# power_mux-v2.net
KiCad netlist of a schematic drawn in EAGLE
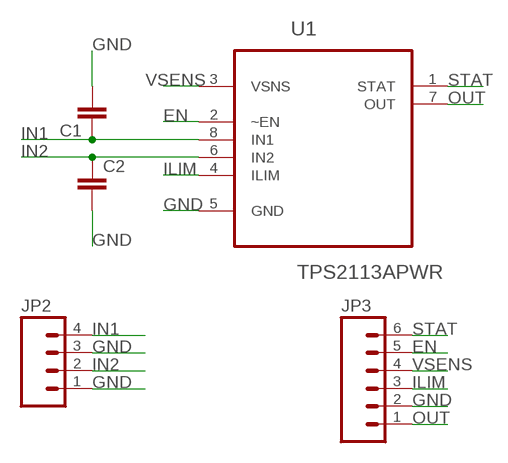
[diagram p0: schematic, sheet 1]

(export (version "E")
  (design (tool "Eeschema 10.0.6"))
  (components
    (comp (ref "C1")
      (value "CAP0805")
      (footprint "eagle-import:0805")
      (libsource (lib "eagle-import") (part "CAP0805"))
    )
    (comp (ref "C2")
      (value "CAP0805")
      (footprint "eagle-import:0805")
      (libsource (lib "eagle-import") (part "CAP0805"))
    )
    (comp (ref "JP2")
      (value "M04PTH")
      (footprint "eagle-import:1X04")
      (libsource (lib "eagle-import") (part "M04PTH"))
    )
    (comp (ref "JP3")
      (value "M06SIP")
      (footprint "eagle-import:1X06")
      (libsource (lib "eagle-import") (part "M06SIP"))
    )
    (comp (ref "U1")
      (value "TPS2113APWR")
      (footprint "eagle-import:SOP65P640X120-8N")
      (libsource (lib "eagle-import") (part "TPS2113APWR"))
    )
  )
  (nets
    (net (code "1") (name "/EN") (class "Default")
      (node (ref "JP3") (pin "5") (pinfunction "5_5") (pintype "passive"))
      (node (ref "U1") (pin "2") (pinfunction "~{EN}_2") (pintype "input"))
    )
    (net (code "2") (name "/GND") (class "Default")
      (node (ref "C1") (pin "2") (pinfunction "2_2") (pintype "passive"))
      (node (ref "C2") (pin "2") (pinfunction "2_2") (pintype "passive"))
      (node (ref "JP2") (pin "1") (pinfunction "1_1") (pintype "passive"))
      (node (ref "JP2") (pin "3") (pinfunction "3_3") (pintype "passive"))
      (node (ref "JP3") (pin "2") (pinfunction "2_2") (pintype "passive"))
      (node (ref "U1") (pin "5") (pinfunction "GND_5") (pintype "passive"))
    )
    (net (code "3") (name "/ILIM") (class "Default")
      (node (ref "JP3") (pin "3") (pinfunction "3_3") (pintype "passive"))
      (node (ref "U1") (pin "4") (pinfunction "ILIM_4") (pintype "input"))
    )
    (net (code "4") (name "/IN1") (class "Default")
      (node (ref "C1") (pin "1") (pinfunction "1_1") (pintype "passive"))
      (node (ref "JP2") (pin "4") (pinfunction "4_4") (pintype "passive"))
      (node (ref "U1") (pin "8") (pinfunction "IN1_8") (pintype "input"))
    )
    (net (code "5") (name "/IN2") (class "Default")
      (node (ref "C2") (pin "1") (pinfunction "1_1") (pintype "passive"))
      (node (ref "JP2") (pin "2") (pinfunction "2_2") (pintype "passive"))
      (node (ref "U1") (pin "6") (pinfunction "IN2_6") (pintype "input"))
    )
    (net (code "6") (name "/OUT") (class "Default")
      (node (ref "JP3") (pin "1") (pinfunction "1_1") (pintype "passive"))
      (node (ref "U1") (pin "7") (pinfunction "OUT_7") (pintype "output"))
    )
    (net (code "7") (name "/STAT") (class "Default")
      (node (ref "JP3") (pin "6") (pinfunction "6_6") (pintype "passive"))
      (node (ref "U1") (pin "1") (pinfunction "STAT_1") (pintype "output"))
    )
    (net (code "8") (name "/VSENS") (class "Default")
      (node (ref "JP3") (pin "4") (pinfunction "4_4") (pintype "passive"))
      (node (ref "U1") (pin "3") (pinfunction "VSNS_3") (pintype "power_in"))
    )
  )
)
